# Motor_Interface_-_Pre-Charge_Interface.net
KiCad netlist of a schematic drawn in Altium Designer
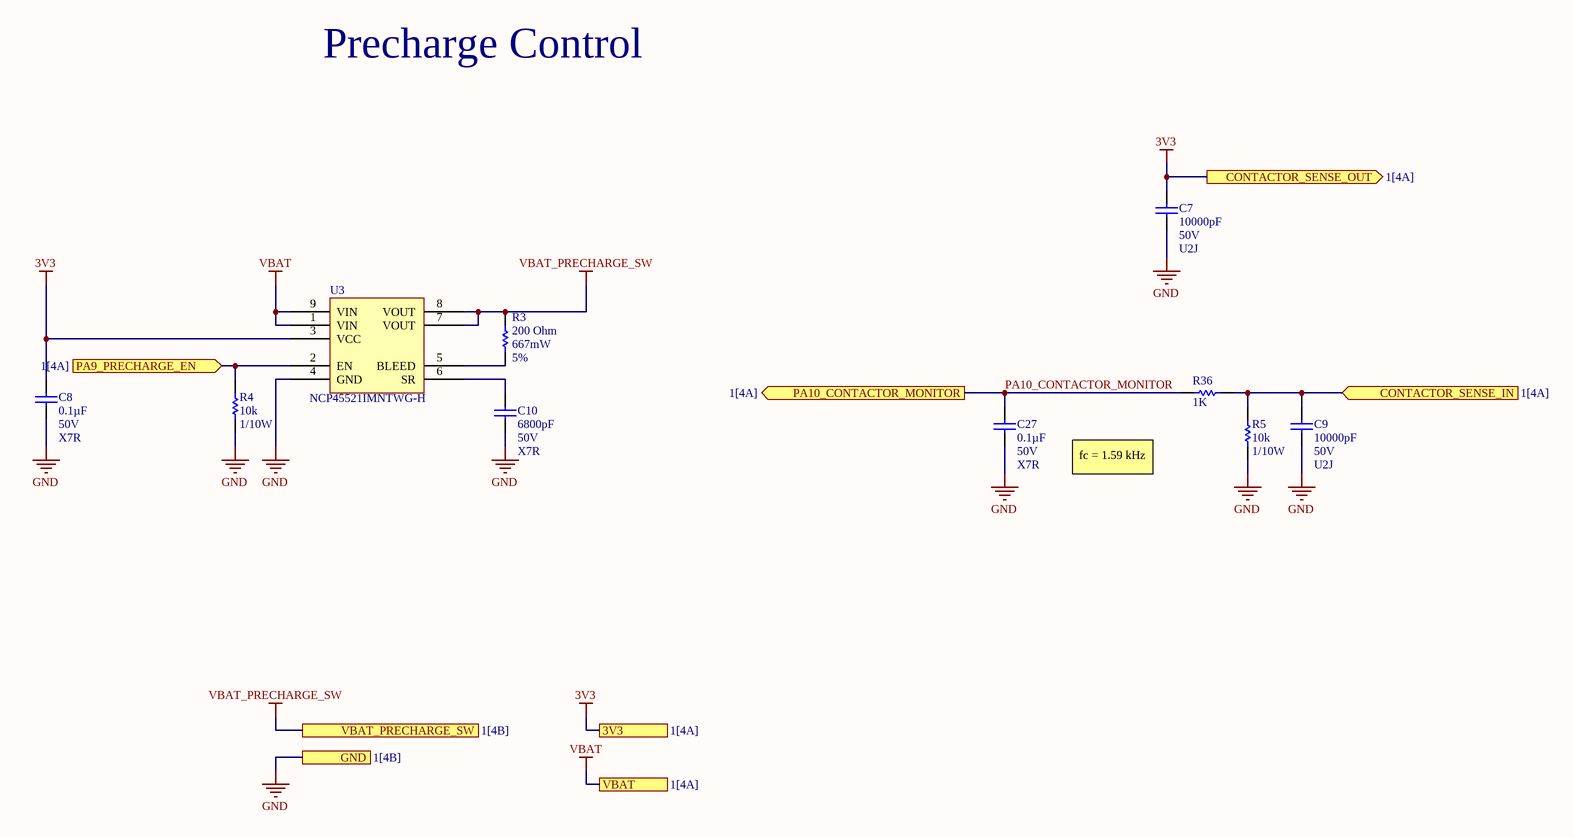
[diagram p0: Motor Interface - Pre-Charge Interface.SchDoc]

(export (version "E")
  (design (tool "Eeschema 10.0.6"))
  (components
    (comp (ref "C7")
      (value "CAP CER 10nF 50V 5% X7R 0603")
      (footprint "CAP, 0603")
      (description "10000pF ±5% 50V Ceramic Capacitor U2J 0603 (1608 Metric)")
      (fields
        (field (name "TOLERANCE") "±5%")
        (field (name "CAPACITANCE") "10000pF")
        (field (name "VOLTAGE") "50V")
        (field (name "TEMPERATURE COEFFICIENT") "U2J")
      )
      (libsource (lib "altium-import") (part "root_0_CAP CER 10nF 50V 5% X7R 0603_"))
    )
    (comp (ref "C8")
      (value "CAP CER 0.1UF 50V 10% X7R 0603")
      (footprint "CAP, 0603")
      (description "0.10µF ±10% 50V Ceramic Capacitor X7R 0603 (1608 Metric)")
      (fields
        (field (name "TOLERANCE") "±10%")
        (field (name "CAPACITANCE") "0.1µF")
        (field (name "VOLTAGE") "50V")
        (field (name "TEMPERATURE COEFFICIENT") "X7R")
      )
      (libsource (lib "Schematic Diagrams") (part "CAP CER 0.1UF 50V 10% X7R 0603"))
    )
    (comp (ref "C9")
      (value "CAP CER 10nF 50V 5% X7R 0603")
      (footprint "CAP, 0603")
      (description "10000pF ±5% 50V Ceramic Capacitor U2J 0603 (1608 Metric)")
      (fields
        (field (name "TOLERANCE") "±5%")
        (field (name "CAPACITANCE") "10000pF")
        (field (name "VOLTAGE") "50V")
        (field (name "TEMPERATURE COEFFICIENT") "U2J")
      )
      (libsource (lib "altium-import") (part "root_0_CAP CER 10nF 50V 5% X7R 0603_"))
    )
    (comp (ref "C10")
      (value "CAP CER 6800pF 50V 10% X7R 0603")
      (footprint "CAP, 0603")
      (description "6800pF ±10% 50V Ceramic Capacitor X7R 0603 (1608 Metric)")
      (fields
        (field (name "TOLERANCE") "±10%")
        (field (name "CAPACITANCE") "6800pF")
        (field (name "VOLTAGE") "50V")
        (field (name "TEMPERATURE COEFFICIENT") "X7R")
      )
      (libsource (lib "altium-import") (part "root_0_CAP CER 6800pF 50V 10% X7R 0603_"))
    )
    (comp (ref "C27")
      (value "CAP CER 0.1UF 50V 10% X7R 0603")
      (footprint "CAP, 0603")
      (description "0.10µF ±10% 50V Ceramic Capacitor X7R 0603 (1608 Metric)")
      (fields
        (field (name "TOLERANCE") "±10%")
        (field (name "CAPACITANCE") "0.1µF")
        (field (name "VOLTAGE") "50V")
        (field (name "TEMPERATURE COEFFICIENT") "X7R")
      )
      (libsource (lib "altium-import") (part "root_0_CAP CER 0.1UF 50V 10% X7R 0603_"))
    )
    (comp (ref "R3")
      (value "200 Ohm")
      (footprint "RES 1206")
      (fields
        (field (name "MANUFACTURER") "Panasonic")
        (field (name "MANUFACTURER PART NUMBER") "ERJ-P08J201V")
        (field (name "TOLERANCE") "5%")
        (field (name "MAX POWER DISSIPATION") "667mW")
      )
      (libsource (lib "Schematic Diagrams") (part "RES 200 OHM 5% 2/3W 1206"))
    )
    (comp (ref "R4")
      (value "RES 10K OHM 1% 1/10W 0603")
      (footprint "RES, 0603")
      (description "RES SMD 10K OHM 1% 1/10W 0603")
      (fields
        (field (name "TOLERANCE") "±1%")
        (field (name "RESISTANCE") "10k")
        (field (name "POWER") "1/10W")
      )
      (libsource (lib "Schematic Diagrams") (part "RES 10K OHM 1% 1/10W 0603"))
    )
    (comp (ref "R5")
      (value "RES 10K OHM 1% 1/10W 0603")
      (footprint "RES, 0603")
      (description "RES SMD 10K OHM 1% 1/10W 0603")
      (fields
        (field (name "TOLERANCE") "±1%")
        (field (name "RESISTANCE") "10k")
        (field (name "POWER") "1/10W")
      )
      (libsource (lib "Schematic Diagrams") (part "RES 10K OHM 1% 1/10W 0603"))
    )
    (comp (ref "R36")
      (value "1K")
      (footprint "RES, 0603")
      (description "1k Ohm ±5% 0.1W, 1/10W Chip Resistor 0603 (1608 Metric)")
      (fields
        (field (name "MANUFACTURER") "Yageo")
        (field (name "MANUFACTURER PART NUMBER") "RC0603JR-071KL")
      )
      (libsource (lib "altium-import") (part "root_1_RES 1K OHM 5% 1/10W 0603_"))
    )
    (comp (ref "U3")
      (value "IC LOAD SWITCH ACT-HI 10.5A 8DFN")
      (footprint "IC LOAD SWITCH ACT-HI 10.5A 8DFN")
      (description "NCP45521IMNTWG-H")
      (fields
        (field (name "MANUFACTURER") "ON Semiconductor")
        (field (name "MANUFACTURER PART NUMBER") "NCP45521IMNTWG-H")
      )
      (libsource (lib "Schematic Diagrams") (part "IC LOAD SWITCH ACT-HI 10.5A 8DFN"))
    )
  )
  (nets
    (net (code "1") (name "/CONTACTOR_SENSE_IN") (class "Default")
      (node (ref "C9") (pin "1") (pinfunction "1_1") (pintype "passive"))
      (node (ref "R36") (pin "2") (pinfunction "2_2") (pintype "passive"))
      (node (ref "R5") (pin "1") (pinfunction "1_1") (pintype "passive"))
    )
    (net (code "2") (name "/PA9_PRECHARGE_EN") (class "Default")
      (node (ref "R4") (pin "1") (pinfunction "1_1") (pintype "passive"))
      (node (ref "U3") (pin "2") (pinfunction "EN_2") (pintype "passive"))
    )
    (net (code "3") (name "/PA10_CONTACTOR_MONITOR") (class "Default")
      (node (ref "C27") (pin "1") (pinfunction "1_1") (pintype "passive"))
      (node (ref "R36") (pin "1") (pinfunction "1_1") (pintype "passive"))
    )
    (net (code "4") (name "3V3") (class "Default")
      (node (ref "C7") (pin "1") (pinfunction "1_1") (pintype "passive"))
      (node (ref "C8") (pin "1") (pinfunction "1_1") (pintype "passive"))
      (node (ref "U3") (pin "3") (pinfunction "VCC_3") (pintype "passive"))
    )
    (net (code "5") (name "GND") (class "Default")
      (node (ref "C10") (pin "2") (pinfunction "2_2") (pintype "passive"))
      (node (ref "C27") (pin "2") (pinfunction "2_2") (pintype "passive"))
      (node (ref "C7") (pin "2") (pinfunction "2_2") (pintype "passive"))
      (node (ref "C8") (pin "2") (pinfunction "2_2") (pintype "passive"))
      (node (ref "C9") (pin "2") (pinfunction "2_2") (pintype "passive"))
      (node (ref "R4") (pin "2") (pinfunction "2_2") (pintype "passive"))
      (node (ref "R5") (pin "2") (pinfunction "2_2") (pintype "passive"))
      (node (ref "U3") (pin "4") (pinfunction "GND_4") (pintype "passive"))
    )
    (net (code "6") (name "Net-(U3-BLEED)") (class "Default")
      (node (ref "R3") (pin "2") (pinfunction "2_2") (pintype "passive"))
      (node (ref "U3") (pin "5") (pinfunction "BLEED_5") (pintype "passive"))
    )
    (net (code "7") (name "Net-(U3-SR)") (class "Default")
      (node (ref "C10") (pin "1") (pinfunction "1_1") (pintype "passive"))
      (node (ref "U3") (pin "6") (pinfunction "SR_6") (pintype "passive"))
    )
    (net (code "8") (name "VBAT") (class "Default")
      (node (ref "U3") (pin "1") (pinfunction "VIN_1") (pintype "passive"))
      (node (ref "U3") (pin "9") (pinfunction "VIN_9") (pintype "passive"))
    )
    (net (code "9") (name "VBAT_PRECHARGE_SW") (class "Default")
      (node (ref "R3") (pin "1") (pinfunction "1_1") (pintype "passive"))
      (node (ref "U3") (pin "7") (pinfunction "VOUT_7") (pintype "passive"))
      (node (ref "U3") (pin "8") (pinfunction "VOUT_8") (pintype "passive"))
    )
  )
)
